# ZED-F9P_NEO-D9S_Combo.net
KiCad netlist of a schematic drawn in EAGLE
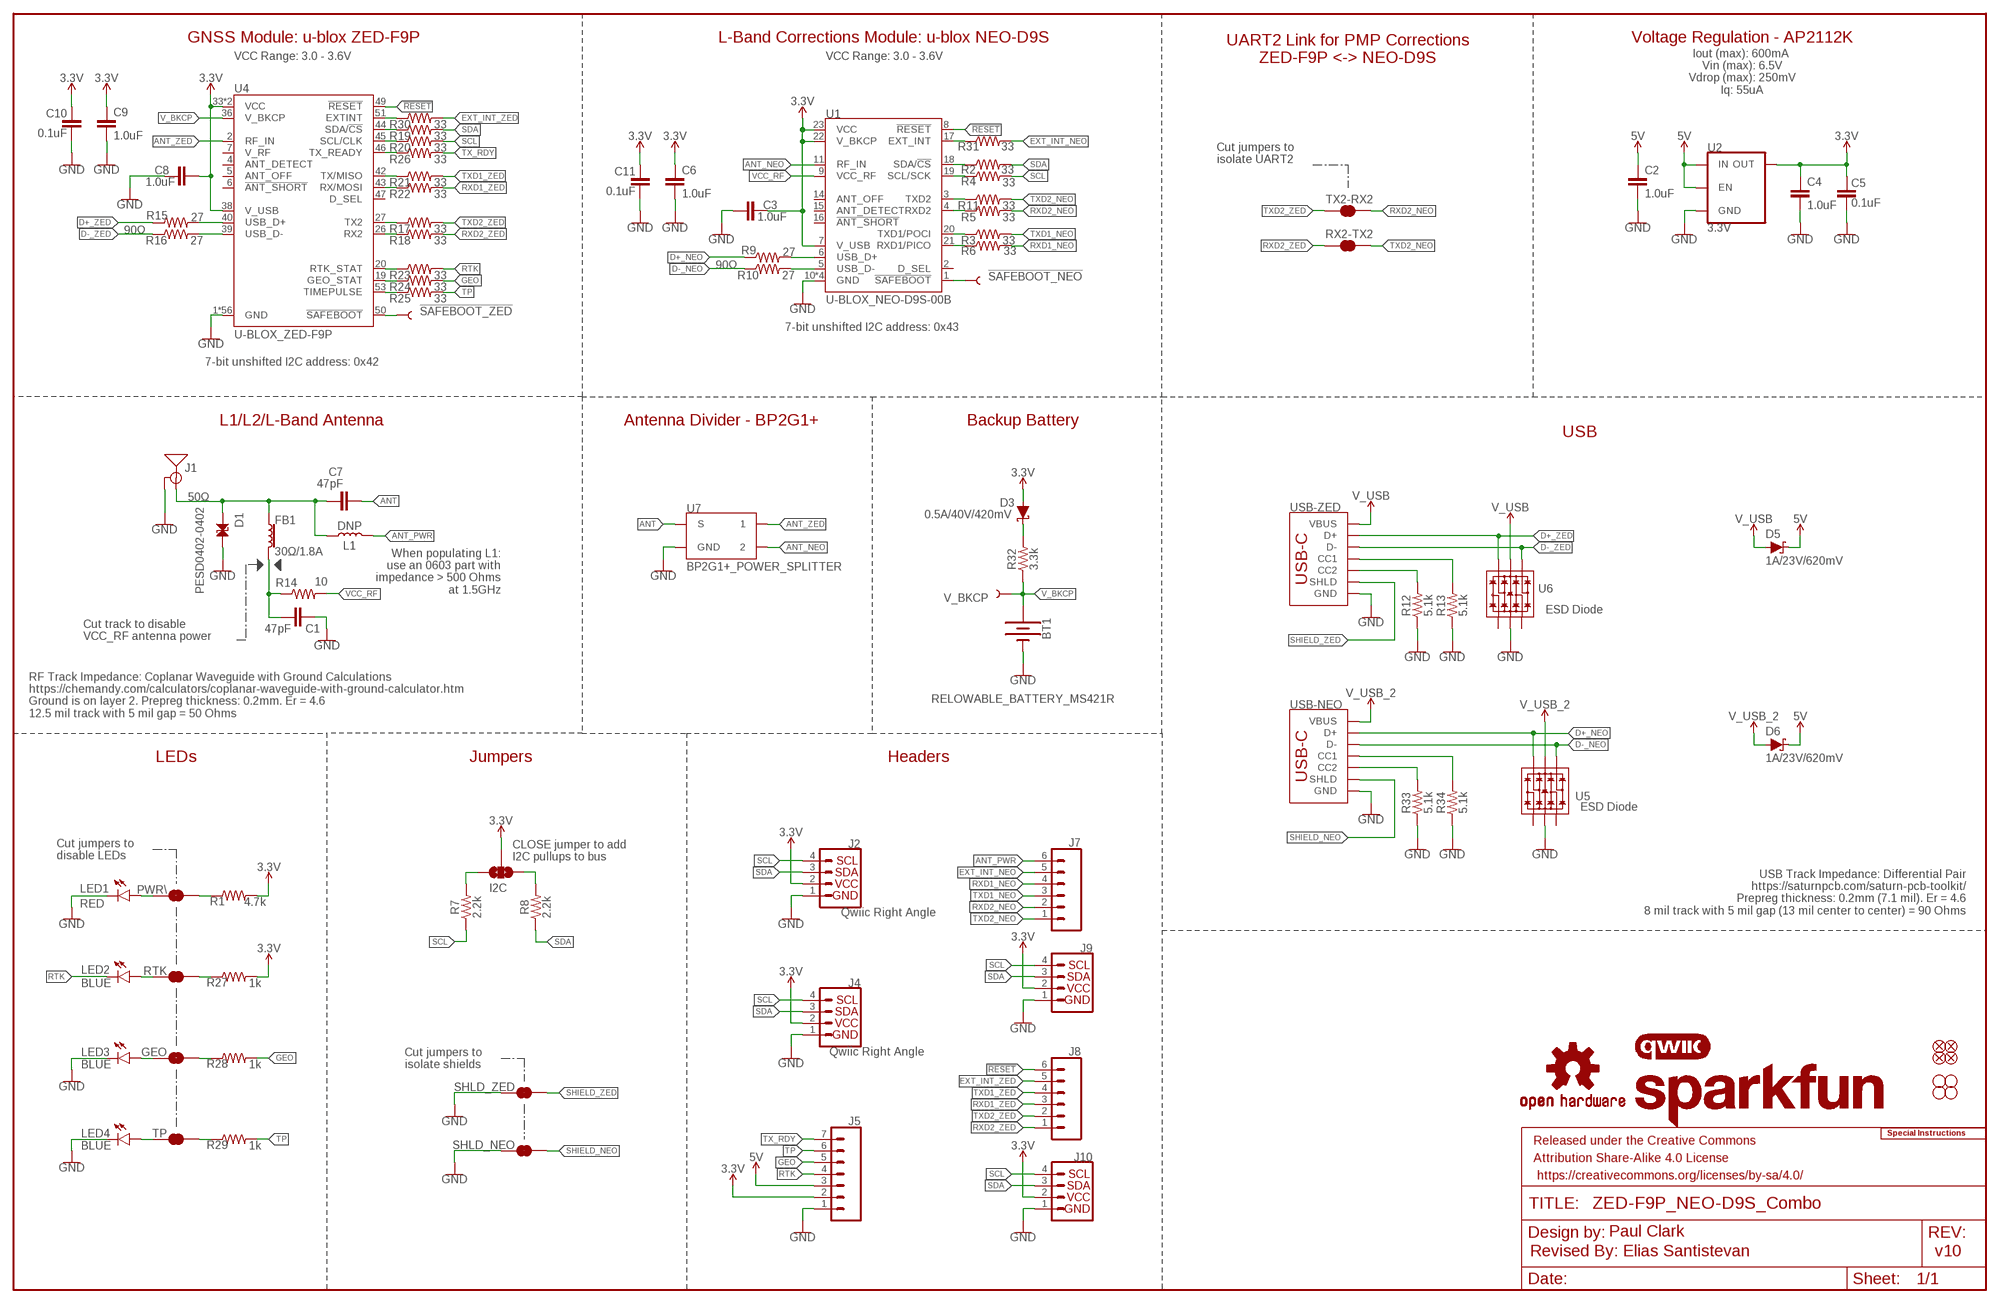
[diagram p0: schematic, sheet 1]

(export (version "E")
  (design (tool "Eeschema 10.0.6"))
  (components
    (comp (ref "!SAFEBOOT_NEO!")
      (value "TEST-POINTPOGO_PTH")
      (footprint "eagle-import:1X01_NO_SILK")
      (libsource (lib "eagle-import") (part "TEST-POINTPOGO_PTH"))
    )
    (comp (ref "!SAFEBOOT_ZED!")
      (value "TEST-POINTPOGO_PTH")
      (footprint "eagle-import:1X01_NO_SILK")
      (libsource (lib "eagle-import") (part "TEST-POINTPOGO_PTH"))
    )
    (comp (ref "BT1")
      (value "RELOWABLE_BATTERY_MS421R")
      (footprint "eagle-import:MS421R_IV03E")
      (libsource (lib "eagle-import") (part "RELOWABLE_BATTERY_MS421R"))
    )
    (comp (ref "C1")
      (value "47pF")
      (footprint "eagle-import:0603")
      (libsource (lib "eagle-import") (part "47PF-0603-50V-5%"))
    )
    (comp (ref "C2")
      (value "1.0uF")
      (footprint "eagle-import:0603")
      (libsource (lib "eagle-import") (part "1.0UF-0603-16V-10%"))
    )
    (comp (ref "C3")
      (value "1.0uF")
      (footprint "eagle-import:0603")
      (libsource (lib "eagle-import") (part "1.0UF-0603-16V-10%"))
    )
    (comp (ref "C4")
      (value "1.0uF")
      (footprint "eagle-import:0603")
      (libsource (lib "eagle-import") (part "1.0UF-0603-16V-10%"))
    )
    (comp (ref "C5")
      (value "0.1uF")
      (footprint "eagle-import:0603")
      (libsource (lib "eagle-import") (part "0.1UF-0603-25V-(+80/-20%)"))
    )
    (comp (ref "C6")
      (value "1.0uF")
      (footprint "eagle-import:0603")
      (libsource (lib "eagle-import") (part "1.0UF-0603-16V-10%"))
    )
    (comp (ref "C7")
      (value "47pF")
      (footprint "eagle-import:0603")
      (libsource (lib "eagle-import") (part "47PF-0603-50V-5%"))
    )
    (comp (ref "C8")
      (value "1.0uF")
      (footprint "eagle-import:0603")
      (libsource (lib "eagle-import") (part "1.0UF-0603-16V-10%"))
    )
    (comp (ref "C9")
      (value "1.0uF")
      (footprint "eagle-import:0603")
      (libsource (lib "eagle-import") (part "1.0UF-0603-16V-10%"))
    )
    (comp (ref "C10")
      (value "0.1uF")
      (footprint "eagle-import:0603")
      (libsource (lib "eagle-import") (part "0.1UF-0603-25V-(+80/-20%)"))
    )
    (comp (ref "C11")
      (value "0.1uF")
      (footprint "eagle-import:0603")
      (libsource (lib "eagle-import") (part "0.1UF-0603-25V-(+80/-20%)"))
    )
    (comp (ref "D1")
      (value "PESD0402-0402")
      (footprint "eagle-import:0402")
      (fields
        (field (name "DIGIKEY_PART") "PESD0402-140CT-ND")
        (field (name "MOUSE_PART") "650-PESD0402-140")
      )
      (libsource (lib "eagle-import") (part "PESD0402-0402"))
    )
    (comp (ref "D3")
      (value "0.5A/40V/420mV")
      (footprint "eagle-import:SOD-323")
      (libsource (lib "eagle-import") (part "DIODE-SCHOTTKY-PMEG4005EJ"))
    )
    (comp (ref "D5")
      (value "1A/23V/620mV")
      (footprint "eagle-import:SOD-323")
      (libsource (lib "eagle-import") (part "DIODE-SCHOTTKY-BAT20J"))
    )
    (comp (ref "D6")
      (value "1A/23V/620mV")
      (footprint "eagle-import:SOD-323")
      (libsource (lib "eagle-import") (part "DIODE-SCHOTTKY-BAT20J"))
    )
    (comp (ref "FB1")
      (value "30Ω/1.8A")
      (footprint "eagle-import:0603")
      (libsource (lib "eagle-import") (part "FERRITE_BEAD-0603"))
    )
    (comp (ref "FRAME2")
      (value "FRAME-LEDGER")
      (footprint "eagle-import:CREATIVE_COMMONS")
      (libsource (lib "eagle-import") (part "FRAME-LEDGER"))
    )
    (comp (ref "GEO")
      (value "JUMPER-SMT_2_NC_TRACE_SILK")
      (footprint "eagle-import:SMT-JUMPER_2_NC_TRACE_SILK")
      (libsource (lib "eagle-import") (part "JUMPER-SMT_2_NC_TRACE_SILK"))
    )
    (comp (ref "I2C")
      (value "JUMPER-SMT_3_NO_SILK")
      (footprint "eagle-import:SMT-JUMPER_3_NO_SILK")
      (libsource (lib "eagle-import") (part "JUMPER-SMT_3_NO_SILK"))
    )
    (comp (ref "J1")
      (value "ANTENNA-SMA-GROUNDEDEDGE_SMA")
      (footprint "eagle-import:SMA-EDGE")
      (libsource (lib "eagle-import") (part "ANTENNA-SMA-GROUNDEDEDGE_SMA"))
    )
    (comp (ref "J2")
      (value "Qwiic Right Angle")
      (footprint "eagle-import:JST04_1MM_RA")
      (libsource (lib "eagle-import") (part "I2C_STANDARDQWIIC"))
    )
    (comp (ref "J4")
      (value "Qwiic Right Angle")
      (footprint "eagle-import:JST04_1MM_RA")
      (libsource (lib "eagle-import") (part "I2C_STANDARDQWIIC"))
    )
    (comp (ref "J5")
      (value "CONN_07NO_SILK")
      (footprint "eagle-import:1X07_NO_SILK")
      (libsource (lib "eagle-import") (part "CONN_07NO_SILK"))
    )
    (comp (ref "J7")
      (value "CONN_06NO_SILK_NO_POP")
      (footprint "eagle-import:1X06_NO_SILK")
      (libsource (lib "eagle-import") (part "CONN_06NO_SILK_NO_POP"))
    )
    (comp (ref "J8")
      (value "CONN_06NO_SILK_NO_POP")
      (footprint "eagle-import:1X06_NO_SILK")
      (libsource (lib "eagle-import") (part "CONN_06NO_SILK_NO_POP"))
    )
    (comp (ref "J9")
      (value "I2C_STANDARD_NO_SILK")
      (footprint "eagle-import:1X04_NO_SILK")
      (libsource (lib "eagle-import") (part "I2C_STANDARD_NO_SILK"))
    )
    (comp (ref "J10")
      (value "I2C_STANDARD_NO_SILK")
      (footprint "eagle-import:1X04_NO_SILK")
      (libsource (lib "eagle-import") (part "I2C_STANDARD_NO_SILK"))
    )
    (comp (ref "JP21")
      (value "FIDUCIALUFIDUCIAL")
      (footprint "eagle-import:MICRO-FIDUCIAL")
      (libsource (lib "eagle-import") (part "FIDUCIALUFIDUCIAL"))
    )
    (comp (ref "JP31")
      (value "STAND-OFF")
      (footprint "eagle-import:STAND-OFF")
      (libsource (lib "eagle-import") (part "STAND-OFF"))
    )
    (comp (ref "JP41")
      (value "STAND-OFF")
      (footprint "eagle-import:STAND-OFF")
      (libsource (lib "eagle-import") (part "STAND-OFF"))
    )
    (comp (ref "JP61")
      (value "FIDUCIALUFIDUCIAL")
      (footprint "eagle-import:MICRO-FIDUCIAL")
      (libsource (lib "eagle-import") (part "FIDUCIALUFIDUCIAL"))
    )
    (comp (ref "JP71")
      (value "FIDUCIALUFIDUCIAL")
      (footprint "eagle-import:MICRO-FIDUCIAL")
      (libsource (lib "eagle-import") (part "FIDUCIALUFIDUCIAL"))
    )
    (comp (ref "JP81")
      (value "FIDUCIALUFIDUCIAL")
      (footprint "eagle-import:MICRO-FIDUCIAL")
      (libsource (lib "eagle-import") (part "FIDUCIALUFIDUCIAL"))
    )
    (comp (ref "JP91")
      (value "STAND-OFF")
      (footprint "eagle-import:STAND-OFF")
      (libsource (lib "eagle-import") (part "STAND-OFF"))
    )
    (comp (ref "JP101")
      (value "STAND-OFF")
      (footprint "eagle-import:STAND-OFF")
      (libsource (lib "eagle-import") (part "STAND-OFF"))
    )
    (comp (ref "L1")
      (value "DNP")
      (footprint "eagle-import:0603_NO-CREAM")
      (libsource (lib "eagle-import") (part "DNP-0603_NO-CREAM"))
    )
    (comp (ref "LED1")
      (value "RED")
      (footprint "eagle-import:LED-0603")
      (libsource (lib "eagle-import") (part "LED-RED_0603-KB"))
    )
    (comp (ref "LED2")
      (value "BLUE")
      (footprint "eagle-import:LED-0603")
      (libsource (lib "eagle-import") (part "LED-BLUE0603"))
    )
    (comp (ref "LED3")
      (value "BLUE")
      (footprint "eagle-import:LED-0603")
      (libsource (lib "eagle-import") (part "LED-BLUE0603"))
    )
    (comp (ref "LED4")
      (value "BLUE")
      (footprint "eagle-import:LED-0603")
      (libsource (lib "eagle-import") (part "LED-BLUE0603"))
    )
    (comp (ref "LOGO2")
      (value "SFE_LOGO_NAME.1_INCH")
      (footprint "eagle-import:SFE_LOGO_NAME_.1")
      (libsource (lib "eagle-import") (part "SFE_LOGO_NAME.1_INCH"))
    )
    (comp (ref "LOGO3")
      (value "QWIIC_LOGO_5MM")
      (footprint "eagle-import:QWIIC_5MM")
      (libsource (lib "eagle-import") (part "QWIIC_LOGO_5MM"))
    )
    (comp (ref "LOGO4")
      (value "OSHW-LOGOS")
      (footprint "eagle-import:OSHW-LOGO-S")
      (libsource (lib "eagle-import") (part "OSHW-LOGOS"))
    )
    (comp (ref "LOGO5")
      (value "SPECIAL_INSTRUCTIONS-ORDERING")
      (footprint "eagle-import:ORDERING_INSTRUCTIONS")
      (libsource (lib "eagle-import") (part "SPECIAL_INSTRUCTIONS-ORDERING"))
    )
    (comp (ref "PWR\\")
      (value "JUMPER-SMT_2_NC_TRACE_SILK")
      (footprint "eagle-import:SMT-JUMPER_2_NC_TRACE_SILK")
      (libsource (lib "eagle-import") (part "JUMPER-SMT_2_NC_TRACE_SILK"))
    )
    (comp (ref "R1")
      (value "4.7k")
      (footprint "eagle-import:0603")
      (libsource (lib "eagle-import") (part "4.7KOHM-0603-1/10W-1%"))
    )
    (comp (ref "R2")
      (value "33")
      (footprint "eagle-import:0603")
      (libsource (lib "eagle-import") (part "33OHM-0603-1/10W-1%"))
    )
    (comp (ref "R3")
      (value "33")
      (footprint "eagle-import:0603")
      (libsource (lib "eagle-import") (part "33OHM-0603-1/10W-1%"))
    )
    (comp (ref "R4")
      (value "33")
      (footprint "eagle-import:0603")
      (libsource (lib "eagle-import") (part "33OHM-0603-1/10W-1%"))
    )
    (comp (ref "R5")
      (value "33")
      (footprint "eagle-import:0603")
      (libsource (lib "eagle-import") (part "33OHM-0603-1/10W-1%"))
    )
    (comp (ref "R6")
      (value "33")
      (footprint "eagle-import:0603")
      (libsource (lib "eagle-import") (part "33OHM-0603-1/10W-1%"))
    )
    (comp (ref "R7")
      (value "2.2k")
      (footprint "eagle-import:0603")
      (libsource (lib "eagle-import") (part "2.2KOHM-0603-1/10W-1%"))
    )
    (comp (ref "R8")
      (value "2.2k")
      (footprint "eagle-import:0603")
      (libsource (lib "eagle-import") (part "2.2KOHM-0603-1/10W-1%"))
    )
    (comp (ref "R9")
      (value "27")
      (footprint "eagle-import:0603")
      (libsource (lib "eagle-import") (part "27OHM-0603-1/10W-1%"))
    )
    (comp (ref "R10")
      (value "27")
      (footprint "eagle-import:0603")
      (libsource (lib "eagle-import") (part "27OHM-0603-1/10W-1%"))
    )
    (comp (ref "R11")
      (value "33")
      (footprint "eagle-import:0603")
      (libsource (lib "eagle-import") (part "33OHM-0603-1/10W-1%"))
    )
    (comp (ref "R12")
      (value "5.1k")
      (footprint "eagle-import:0603")
      (libsource (lib "eagle-import") (part "5.1KOHM5.1KOHM-0603-1/10W-1%"))
    )
    (comp (ref "R13")
      (value "5.1k")
      (footprint "eagle-import:0603")
      (libsource (lib "eagle-import") (part "5.1KOHM5.1KOHM-0603-1/10W-1%"))
    )
    (comp (ref "R14")
      (value "10")
      (footprint "eagle-import:0603")
      (libsource (lib "eagle-import") (part "10OHM-0603-1/10W-1%"))
    )
    (comp (ref "R15")
      (value "27")
      (footprint "eagle-import:0603")
      (libsource (lib "eagle-import") (part "27OHM-0603-1/10W-1%"))
    )
    (comp (ref "R16")
      (value "27")
      (footprint "eagle-import:0603")
      (libsource (lib "eagle-import") (part "27OHM-0603-1/10W-1%"))
    )
    (comp (ref "R17")
      (value "33")
      (footprint "eagle-import:0603")
      (libsource (lib "eagle-import") (part "33OHM-0603-1/10W-1%"))
    )
    (comp (ref "R18")
      (value "33")
      (footprint "eagle-import:0603")
      (libsource (lib "eagle-import") (part "33OHM-0603-1/10W-1%"))
    )
    (comp (ref "R19")
      (value "33")
      (footprint "eagle-import:0603")
      (libsource (lib "eagle-import") (part "33OHM-0603-1/10W-1%"))
    )
    (comp (ref "R20")
      (value "33")
      (footprint "eagle-import:0603")
      (libsource (lib "eagle-import") (part "33OHM-0603-1/10W-1%"))
    )
    (comp (ref "R21")
      (value "33")
      (footprint "eagle-import:0603")
      (libsource (lib "eagle-import") (part "33OHM-0603-1/10W-1%"))
    )
    (comp (ref "R22")
      (value "33")
      (footprint "eagle-import:0603")
      (libsource (lib "eagle-import") (part "33OHM-0603-1/10W-1%"))
    )
    (comp (ref "R23")
      (value "33")
      (footprint "eagle-import:0603")
      (libsource (lib "eagle-import") (part "33OHM-0603-1/10W-1%"))
    )
    (comp (ref "R24")
      (value "33")
      (footprint "eagle-import:0603")
      (libsource (lib "eagle-import") (part "33OHM-0603-1/10W-1%"))
    )
    (comp (ref "R25")
      (value "33")
      (footprint "eagle-import:0603")
      (libsource (lib "eagle-import") (part "33OHM-0603-1/10W-1%"))
    )
    (comp (ref "R26")
      (value "33")
      (footprint "eagle-import:0603")
      (libsource (lib "eagle-import") (part "33OHM-0603-1/10W-1%"))
    )
    (comp (ref "R27")
      (value "1k")
      (footprint "eagle-import:0603")
      (libsource (lib "eagle-import") (part "1KOHM-0603-1/10W-1%"))
    )
    (comp (ref "R28")
      (value "1k")
      (footprint "eagle-import:0603")
      (libsource (lib "eagle-import") (part "1KOHM-0603-1/10W-1%"))
    )
    (comp (ref "R29")
      (value "1k")
      (footprint "eagle-import:0603")
      (libsource (lib "eagle-import") (part "1KOHM-0603-1/10W-1%"))
    )
    (comp (ref "R30")
      (value "33")
      (footprint "eagle-import:0603")
      (libsource (lib "eagle-import") (part "33OHM-0603-1/10W-1%"))
    )
    (comp (ref "R31")
      (value "33")
      (footprint "eagle-import:0603")
      (libsource (lib "eagle-import") (part "33OHM-0603-1/10W-1%"))
    )
    (comp (ref "R32")
      (value "3.3k")
      (footprint "eagle-import:0603")
      (libsource (lib "eagle-import") (part "3.3KOHM-0603-1/10W-1%"))
    )
    (comp (ref "R33")
      (value "5.1k")
      (footprint "eagle-import:0603")
      (libsource (lib "eagle-import") (part "5.1KOHM5.1KOHM-0603-1/10W-1%"))
    )
    (comp (ref "R34")
      (value "5.1k")
      (footprint "eagle-import:0603")
      (libsource (lib "eagle-import") (part "5.1KOHM5.1KOHM-0603-1/10W-1%"))
    )
    (comp (ref "RTK")
      (value "JUMPER-SMT_2_NC_TRACE_SILK")
      (footprint "eagle-import:SMT-JUMPER_2_NC_TRACE_SILK")
      (libsource (lib "eagle-import") (part "JUMPER-SMT_2_NC_TRACE_SILK"))
    )
    (comp (ref "RX2-TX2")
      (value "JUMPER-SMT_2_NC_TRACE_SILK")
      (footprint "eagle-import:SMT-JUMPER_2_NC_TRACE_SILK")
      (libsource (lib "eagle-import") (part "JUMPER-SMT_2_NC_TRACE_SILK"))
    )
    (comp (ref "SHLD_NEO")
      (value "JUMPER-SMT_2_NC_TRACE_SILK")
      (footprint "eagle-import:SMT-JUMPER_2_NC_TRACE_SILK")
      (libsource (lib "eagle-import") (part "JUMPER-SMT_2_NC_TRACE_SILK"))
    )
    (comp (ref "SHLD_ZED")
      (value "JUMPER-SMT_2_NC_TRACE_SILK")
      (footprint "eagle-import:SMT-JUMPER_2_NC_TRACE_SILK")
      (libsource (lib "eagle-import") (part "JUMPER-SMT_2_NC_TRACE_SILK"))
    )
    (comp (ref "TP")
      (value "JUMPER-SMT_2_NC_TRACE_SILK")
      (footprint "eagle-import:SMT-JUMPER_2_NC_TRACE_SILK")
      (libsource (lib "eagle-import") (part "JUMPER-SMT_2_NC_TRACE_SILK"))
    )
    (comp (ref "TX2-RX2")
      (value "JUMPER-SMT_2_NC_TRACE_SILK")
      (footprint "eagle-import:SMT-JUMPER_2_NC_TRACE_SILK")
      (libsource (lib "eagle-import") (part "JUMPER-SMT_2_NC_TRACE_SILK"))
    )
    (comp (ref "U1")
      (value "U-BLOX_NEO-D9S-00B")
      (footprint "eagle-import:NEO-M9N_M8T_M8U_D9S")
      (libsource (lib "eagle-import") (part "U-BLOX_NEO-D9S-00B"))
    )
    (comp (ref "U2")
      (value "3.3V")
      (footprint "eagle-import:SOT23-5")
      (libsource (lib "eagle-import") (part "V_REG_AP2112K-3.3V"))
    )
    (comp (ref "U4")
      (value "U-BLOX_ZED-F9P")
      (footprint "eagle-import:ZED-F9P")
      (libsource (lib "eagle-import") (part "U-BLOX_ZED-F9P"))
    )
    (comp (ref "U5")
      (value "ESD Diode")
      (footprint "eagle-import:SOT-23-6")
      (libsource (lib "eagle-import") (part "TVS_DIODE_ARRAY_DT1042-04SO-7"))
    )
    (comp (ref "U6")
      (value "ESD Diode")
      (footprint "eagle-import:SOT-23-6")
      (libsource (lib "eagle-import") (part "TVS_DIODE_ARRAY_DT1042-04SO-7"))
    )
    (comp (ref "U7")
      (value "BP2G1+_POWER_SPLITTER")
      (footprint "eagle-import:XX21")
      (libsource (lib "eagle-import") (part "BP2G1+_POWER_SPLITTER"))
    )
    (comp (ref "USB-NEO")
      (value "USB Female Type C Connector")
      (footprint "eagle-import:USB-C-16P_4LAYER-PADS")
      (libsource (lib "eagle-import") (part "USB_C_4-LAYER_PADS"))
    )
    (comp (ref "USB-ZED")
      (value "USB Female Type C Connector")
      (footprint "eagle-import:USB-C-16P_4LAYER-PADS")
      (libsource (lib "eagle-import") (part "USB_C_4-LAYER_PADS"))
    )
    (comp (ref "V_BKCP")
      (value "TEST-POINT3X5")
      (footprint "eagle-import:PAD.03X.05")
      (libsource (lib "eagle-import") (part "TEST-POINT3X5"))
    )
  )
  (nets
    (net (code "1") (name "/~{RESET}") (class "Default")
      (node (ref "J8") (pin "6") (pinfunction "6_6") (pintype "passive"))
      (node (ref "U1") (pin "8") (pinfunction "~{RESET}_8") (pintype "input"))
      (node (ref "U4") (pin "49") (pinfunction "~{RESET}_49") (pintype "bidirectional"))
    )
    (net (code "2") (name "3.3V") (class "Default")
      (node (ref "C10") (pin "2") (pinfunction "2_2") (pintype "passive"))
      (node (ref "C11") (pin "2") (pinfunction "2_2") (pintype "passive"))
      (node (ref "C3") (pin "1") (pinfunction "1_1") (pintype "passive"))
      (node (ref "C4") (pin "1") (pinfunction "1_1") (pintype "passive"))
      (node (ref "C5") (pin "2") (pinfunction "2_2") (pintype "passive"))
      (node (ref "C6") (pin "1") (pinfunction "1_1") (pintype "passive"))
      (node (ref "C8") (pin "2") (pinfunction "2_2") (pintype "passive"))
      (node (ref "C9") (pin "1") (pinfunction "1_1") (pintype "passive"))
      (node (ref "D3") (pin "A") (pinfunction "A_A") (pintype "passive"))
      (node (ref "I2C") (pin "2") (pinfunction "2_2") (pintype "passive"))
      (node (ref "J10") (pin "2") (pinfunction "2_2") (pintype "power_in"))
      (node (ref "J2") (pin "2") (pinfunction "2_2") (pintype "power_in"))
      (node (ref "J4") (pin "2") (pinfunction "2_2") (pintype "power_in"))
      (node (ref "J5") (pin "2") (pinfunction "2_2") (pintype "passive"))
      (node (ref "J9") (pin "2") (pinfunction "2_2") (pintype "power_in"))
      (node (ref "R1") (pin "2") (pinfunction "2_2") (pintype "passive"))
      (node (ref "R27") (pin "2") (pinfunction "2_2") (pintype "passive"))
      (node (ref "U1") (pin "22") (pinfunction "V_BKCP_22") (pintype "power_in"))
      (node (ref "U1") (pin "23") (pinfunction "VCC_23") (pintype "power_in"))
      (node (ref "U1") (pin "7") (pinfunction "V_USB_7") (pintype "power_in"))
      (node (ref "U2") (pin "5") (pinfunction "OUT_5") (pintype "passive"))
      (node (ref "U4") (pin "33") (pinfunction "VCC_33") (pintype "bidirectional"))
      (node (ref "U4") (pin "34") (pinfunction "VCC_34") (pintype "bidirectional"))
      (node (ref "U4") (pin "38") (pinfunction "V_USB_38") (pintype "bidirectional"))
    )
    (net (code "3") (name "5V") (class "Default")
      (node (ref "C2") (pin "1") (pinfunction "1_1") (pintype "passive"))
      (node (ref "D5") (pin "C") (pinfunction "C_C") (pintype "passive"))
      (node (ref "D6") (pin "C") (pinfunction "C_C") (pintype "passive"))
      (node (ref "J5") (pin "3") (pinfunction "3_3") (pintype "passive"))
      (node (ref "U2") (pin "1") (pinfunction "IN_1") (pintype "input"))
      (node (ref "U2") (pin "3") (pinfunction "EN_3") (pintype "input"))
    )
    (net (code "4") (name "ANT") (class "Default")
      (node (ref "C7") (pin "2") (pinfunction "2_2") (pintype "passive"))
      (node (ref "U7") (pin "2") (pinfunction "S_2") (pintype "bidirectional"))
    )
    (net (code "5") (name "ANT_NEO") (class "Default")
      (node (ref "U1") (pin "11") (pinfunction "RF_IN_11") (pintype "input"))
      (node (ref "U7") (pin "5") (pinfunction "2_5") (pintype "bidirectional"))
    )
    (net (code "6") (name "ANT_PWR") (class "Default")
      (node (ref "J7") (pin "6") (pinfunction "6_6") (pintype "passive"))
      (node (ref "L1") (pin "2") (pinfunction "2_2") (pintype "passive"))
    )
    (net (code "7") (name "ANT_ZED") (class "Default")
      (node (ref "U4") (pin "2") (pinfunction "RF_IN_2") (pintype "bidirectional"))
      (node (ref "U7") (pin "8") (pinfunction "1_8") (pintype "bidirectional"))
    )
    (net (code "8") (name "D+_NEO") (class "Default")
      (node (ref "R9") (pin "1") (pinfunction "1_1") (pintype "passive"))
      (node (ref "U5") (pin "6") (pinfunction "IO4_6") (pintype "bidirectional"))
      (node (ref "USB-NEO") (pin "A6") (pinfunction "D+_A6") (pintype "bidirectional"))
      (node (ref "USB-NEO") (pin "B6") (pinfunction "D+_B6") (pintype "bidirectional"))
    )
    (net (code "9") (name "D+_ZED") (class "Default")
      (node (ref "R15") (pin "1") (pinfunction "1_1") (pintype "passive"))
      (node (ref "U6") (pin "6") (pinfunction "IO4_6") (pintype "bidirectional"))
      (node (ref "USB-ZED") (pin "A6") (pinfunction "D+_A6") (pintype "bidirectional"))
      (node (ref "USB-ZED") (pin "B6") (pinfunction "D+_B6") (pintype "bidirectional"))
    )
    (net (code "10") (name "D-_NEO") (class "Default")
      (node (ref "R10") (pin "1") (pinfunction "1_1") (pintype "passive"))
      (node (ref "U5") (pin "4") (pinfunction "IO3_4") (pintype "bidirectional"))
      (node (ref "USB-NEO") (pin "A7") (pinfunction "D-_A7") (pintype "bidirectional"))
      (node (ref "USB-NEO") (pin "B7") (pinfunction "D-_B7") (pintype "bidirectional"))
    )
    (net (code "11") (name "D-_ZED") (class "Default")
      (node (ref "R16") (pin "1") (pinfunction "1_1") (pintype "passive"))
      (node (ref "U6") (pin "4") (pinfunction "IO3_4") (pintype "bidirectional"))
      (node (ref "USB-ZED") (pin "A7") (pinfunction "D-_A7") (pintype "bidirectional"))
      (node (ref "USB-ZED") (pin "B7") (pinfunction "D-_B7") (pintype "bidirectional"))
    )
    (net (code "12") (name "EXT_INT_NEO") (class "Default")
      (node (ref "J7") (pin "5") (pinfunction "5_5") (pintype "passive"))
      (node (ref "R31") (pin "2") (pinfunction "2_2") (pintype "passive"))
    )
    (net (code "13") (name "EXT_INT_ZED") (class "Default")
      (node (ref "J8") (pin "5") (pinfunction "5_5") (pintype "passive"))
      (node (ref "R30") (pin "2") (pinfunction "2_2") (pintype "passive"))
    )
    (net (code "14") (name "GEO") (class "Default")
      (node (ref "J5") (pin "5") (pinfunction "5_5") (pintype "passive"))
      (node (ref "R24") (pin "2") (pinfunction "2_2") (pintype "passive"))
      (node (ref "R28") (pin "2") (pinfunction "2_2") (pintype "passive"))
    )
    (net (code "15") (name "GND") (class "Default")
      (node (ref "BT1") (pin "-") (pinfunction "-_-") (pintype "power_in"))
      (node (ref "C1") (pin "2") (pinfunction "2_2") (pintype "passive"))
      (node (ref "C10") (pin "1") (pinfunction "1_1") (pintype "passive"))
      (node (ref "C11") (pin "1") (pinfunction "1_1") (pintype "passive"))
      (node (ref "C2") (pin "2") (pinfunction "2_2") (pintype "passive"))
      (node (ref "C3") (pin "2") (pinfunction "2_2") (pintype "passive"))
      (node (ref "C4") (pin "2") (pinfunction "2_2") (pintype "passive"))
      (node (ref "C5") (pin "1") (pinfunction "1_1") (pintype "passive"))
      (node (ref "C6") (pin "2") (pinfunction "2_2") (pintype "passive"))
      (node (ref "C8") (pin "1") (pinfunction "1_1") (pintype "passive"))
      (node (ref "C9") (pin "2") (pinfunction "2_2") (pintype "passive"))
      (node (ref "D1") (pin "2") (pinfunction "2_2") (pintype "bidirectional"))
      (node (ref "J1") (pin "GND@0") (pinfunction "GND_GND@0") (pintype "bidirectional"))
      (node (ref "J1") (pin "GND@1") (pinfunction "GND_GND@1") (pintype "bidirectional"))
      (node (ref "J1") (pin "GND@2") (pinfunction "GND_GND@2") (pintype "bidirectional"))
      (node (ref "J1") (pin "GND@3") (pinfunction "GND_GND@3") (pintype "bidirectional"))
      (node (ref "J10") (pin "1") (pinfunction "1_1") (pintype "power_in"))
      (node (ref "J2") (pin "1") (pinfunction "1_1") (pintype "power_in"))
      (node (ref "J4") (pin "1") (pinfunction "1_1") (pintype "power_in"))
      (node (ref "J5") (pin "1") (pinfunction "1_1") (pintype "passive"))
      (node (ref "J9") (pin "1") (pinfunction "1_1") (pintype "power_in"))
      (node (ref "LED1") (pin "C") (pinfunction "C_C") (pintype "passive"))
      (node (ref "LED3") (pin "C") (pinfunction "C_C") (pintype "passive"))
      (node (ref "LED4") (pin "C") (pinfunction "C_C") (pintype "passive"))
      (node (ref "R12") (pin "1") (pinfunction "1_1") (pintype "passive"))
      (node (ref "R13") (pin "1") (pinfunction "1_1") (pintype "passive"))
      (node (ref "R33") (pin "1") (pinfunction "1_1") (pintype "passive"))
      (node (ref "R34") (pin "1") (pinfunction "1_1") (pintype "passive"))
      (node (ref "SHLD_NEO") (pin "1") (pinfunction "1_1") (pintype "passive"))
      (node (ref "SHLD_ZED") (pin "1") (pinfunction "1_1") (pintype "passive"))
      (node (ref "U1") (pin "10") (pinfunction "GND_10") (pintype "power_in"))
      (node (ref "U1") (pin "12") (pinfunction "GND_12") (pintype "power_in"))
      (node (ref "U1") (pin "13") (pinfunction "GND_13") (pintype "power_in"))
      (node (ref "U1") (pin "24") (pinfunction "GND_24") (pintype "power_in"))
      (node (ref "U2") (pin "2") (pinfunction "GND_2") (pintype "input"))
      (node (ref "U4") (pin "1") (pinfunction "GND_1") (pintype "bidirectional"))
      (node (ref "U4") (pin "100") (pinfunction "GND_100") (pintype "bidirectional"))
      (node (ref "U4") (pin "101") (pinfunction "GND_101") (pintype "bidirectional"))
      (node (ref "U4") (pin "102") (pinfunction "GND_102") (pintype "bidirectional"))
      (node (ref "U4") (pin "12") (pinfunction "GND_12") (pintype "bidirectional"))
      (node (ref "U4") (pin "14") (pinfunction "GND_14") (pintype "bidirectional"))
      (node (ref "U4") (pin "3") (pinfunction "GND_3") (pintype "bidirectional"))
      (node (ref "U4") (pin "32") (pinfunction "GND_32") (pintype "bidirectional"))
      (node (ref "U4") (pin "37") (pinfunction "GND_37") (pintype "bidirectional"))
      (node (ref "U4") (pin "41") (pinfunction "GND_41") (pintype "bidirectional"))
      (node (ref "U4") (pin "48") (pinfunction "GND_48") (pintype "bidirectional"))
      (node (ref "U4") (pin "55") (pinfunction "GND_55") (pintype "bidirectional"))
      (node (ref "U4") (pin "56") (pinfunction "GND_56") (pintype "bidirectional"))
      (node (ref "U4") (pin "57") (pinfunction "GND_57") (pintype "bidirectional"))
      (node (ref "U4") (pin "58") (pinfunction "GND_58") (pintype "bidirectional"))
      (node (ref "U4") (pin "59") (pinfunction "GND_59") (pintype "bidirectional"))
      (node (ref "U4") (pin "60") (pinfunction "GND_60") (pintype "bidirectional"))
      (node (ref "U4") (pin "61") (pinfunction "GND_61") (pintype "bidirectional"))
      (node (ref "U4") (pin "62") (pinfunction "GND_62") (pintype "bidirectional"))
      (node (ref "U4") (pin "63") (pinfunction "GND_63") (pintype "bidirectional"))
      (node (ref "U4") (pin "64") (pinfunction "GND_64") (pintype "bidirectional"))
      (node (ref "U4") (pin "65") (pinfunction "GND_65") (pintype "bidirectional"))
      (node (ref "U4") (pin "66") (pinfunction "GND_66") (pintype "bidirectional"))
      (node (ref "U4") (pin "67") (pinfunction "GND_67") (pintype "bidirectional"))
      (node (ref "U4") (pin "68") (pinfunction "GND_68") (pintype "bidirectional"))
      (node (ref "U4") (pin "69") (pinfunction "GND_69") (pintype "bidirectional"))
      (node (ref "U4") (pin "70") (pinfunction "GND_70") (pintype "bidirectional"))
      (node (ref "U4") (pin "71") (pinfunction "GND_71") (pintype "bidirectional"))
      (node (ref "U4") (pin "72") (pinfunction "GND_72") (pintype "bidirectional"))
      (node (ref "U4") (pin "73") (pinfunction "GND_73") (pintype "bidirectional"))
      (node (ref "U4") (pin "74") (pinfunction "GND_74") (pintype "bidirectional"))
      (node (ref "U4") (pin "75") (pinfunction "GND_75") (pintype "bidirectional"))
      (node (ref "U4") (pin "76") (pinfunction "GND_76") (pintype "bidirectional"))
      (node (ref "U4") (pin "77") (pinfunction "GND_77") (pintype "bidirectional"))
      (node (ref "U4") (pin "78") (pinfunction "GND_78") (pintype "bidirectional"))
      (node (ref "U4") (pin "79") (pinfunction "GND_79") (pintype "bidirectional"))
      (node (ref "U4") (pin "80") (pinfunction "GND_80") (pintype "bidirectional"))
      (node (ref "U4") (pin "81") (pinfunction "GND_81") (pintype "bidirectional"))
      (node (ref "U4") (pin "82") (pinfunction "GND_82") (pintype "bidirectional"))
      (node (ref "U4") (pin "83") (pinfunction "GND_83") (pintype "bidirectional"))
      (node (ref "U4") (pin "84") (pinfunction "GND_84") (pintype "bidirectional"))
      (node (ref "U4") (pin "85") (pinfunction "GND_85") (pintype "bidirectional"))
      (node (ref "U4") (pin "86") (pinfunction "GND_86") (pintype "bidirectional"))
      (node (ref "U4") (pin "87") (pinfunction "GND_87") (pintype "bidirectional"))
      (node (ref "U4") (pin "88") (pinfunction "GND_88") (pintype "bidirectional"))
      (node (ref "U4") (pin "89") (pinfunction "GND_89") (pintype "bidirectional"))
      (node (ref "U4") (pin "90") (pinfunction "GND_90") (pintype "bidirectional"))
      (node (ref "U4") (pin "91") (pinfunction "GND_91") (pintype "bidirectional"))
      (node (ref "U4") (pin "92") (pinfunction "GND_92") (pintype "bidirectional"))
      (node (ref "U4") (pin "93") (pinfunction "GND_93") (pintype "bidirectional"))
      (node (ref "U4") (pin "94") (pinfunction "GND_94") (pintype "bidirectional"))
      (node (ref "U4") (pin "95") (pinfunction "GND_95") (pintype "bidirectional"))
      (node (ref "U4") (pin "96") (pinfunction "GND_96") (pintype "bidirectional"))
      (node (ref "U4") (pin "97") (pinfunction "GND_97") (pintype "bidirectional"))
      (node (ref "U4") (pin "98") (pinfunction "GND_98") (pintype "bidirectional"))
      (node (ref "U4") (pin "99") (pinfunction "GND_99") (pintype "bidirectional"))
      (node (ref "U5") (pin "2") (pinfunction "VSS_2") (pintype "bidirectional"))
      (node (ref "U6") (pin "2") (pinfunction "VSS_2") (pintype "bidirectional"))
      (node (ref "U7") (pin "1") (pinfunction "GND_1") (pintype "bidirectional"))
      (node (ref "U7") (pin "3") (pinfunction "GND_3") (pintype "bidirectional"))
      (node (ref "U7") (pin "4") (pinfunction "GND_4") (pintype "bidirectional"))
      (node (ref "U7") (pin "6") (pinfunction "GND_6") (pintype "bidirectional"))
      (node (ref "U7") (pin "7") (pinfunction "GND_7") (pintype "bidirectional"))
      (node (ref "USB-NEO") (pin "GND") (pinfunction "GND_GND") (pintype "bidirectional"))
      (node (ref "USB-NEO") (pin "GND2") (pinfunction "GND_GND2") (pintype "bidirectional"))
      (node (ref "USB-ZED") (pin "GND") (pinfunction "GND_GND") (pintype "bidirectional"))
      (node (ref "USB-ZED") (pin "GND2") (pinfunction "GND_GND2") (pintype "bidirectional"))
    )
    (net (code "16") (name "Net-(C1-Pad1)") (class "Default")
      (node (ref "C1") (pin "1") (pinfunction "1_1") (pintype "passive"))
      (node (ref "FB1") (pin "2") (pinfunction "2_2") (pintype "passive"))
      (node (ref "R14") (pin "1") (pinfunction "1_1") (pintype "passive"))
    )
    (net (code "17") (name "Net-(D3-PadC)") (class "Default")
      (node (ref "D3") (pin "C") (pinfunction "C_C") (pintype "passive"))
      (node (ref "R32") (pin "2") (pinfunction "2_2") (pintype "passive"))
    )
    (net (code "18") (name "Net-(GEO-Pad1)") (class "Default")
      (node (ref "GEO") (pin "1") (pinfunction "1_1") (pintype "passive"))
      (node (ref "LED3") (pin "A") (pinfunction "A_A") (pintype "passive"))
    )
    (net (code "19") (name "Net-(GEO-Pad2)") (class "Default")
      (node (ref "GEO") (pin "2") (pinfunction "2_2") (pintype "passive"))
      (node (ref "R28") (pin "1") (pinfunction "1_1") (pintype "passive"))
    )
    (net (code "20") (name "Net-(I2C-Pad1)") (class "Default")
      (node (ref "I2C") (pin "1") (pinfunction "1_1") (pintype "passive"))
      (node (ref "R8") (pin "2") (pinfunction "2_2") (pintype "passive"))
    )
    (net (code "21") (name "Net-(I2C-Pad3)") (class "Default")
      (node (ref "I2C") (pin "3") (pinfunction "3_3") (pintype "passive"))
      (node (ref "R7") (pin "2") (pinfunction "2_2") (pintype "passive"))
    )
    (net (code "22") (name "Net-(J1-SIGNAL)") (class "Default")
      (node (ref "C7") (pin "1") (pinfunction "1_1") (pintype "passive"))
      (node (ref "D1") (pin "1") (pinfunction "1_1") (pintype "bidirectional"))
      (node (ref "FB1") (pin "1") (pinfunction "1_1") (pintype "passive"))
      (node (ref "J1") (pin "SIG") (pinfunction "SIGNAL_SIG") (pintype "bidirectional"))
      (node (ref "L1") (pin "1") (pinfunction "1_1") (pintype "passive"))
    )
    (net (code "23") (name "Net-(LED1-PadA)") (class "Default")
      (node (ref "LED1") (pin "A") (pinfunction "A_A") (pintype "passive"))
      (node (ref "PWR\\") (pin "1") (pinfunction "1_1") (pintype "passive"))
    )
    (net (code "24") (name "Net-(LED2-PadA)") (class "Default")
      (node (ref "LED2") (pin "A") (pinfunction "A_A") (pintype "passive"))
      (node (ref "RTK") (pin "1") (pinfunction "1_1") (pintype "passive"))
    )
    (net (code "25") (name "Net-(LED4-PadA)") (class "Default")
      (node (ref "LED4") (pin "A") (pinfunction "A_A") (pintype "passive"))
      (node (ref "TP") (pin "1") (pinfunction "1_1") (pintype "passive"))
    )
    (net (code "26") (name "Net-(PWR\\-Pad2)") (class "Default")
      (node (ref "PWR\\") (pin "2") (pinfunction "2_2") (pintype "passive"))
      (node (ref "R1") (pin "1") (pinfunction "1_1") (pintype "passive"))
    )
    (net (code "27") (name "Net-(R27-Pad1)") (class "Default")
      (node (ref "R27") (pin "1") (pinfunction "1_1") (pintype "passive"))
      (node (ref "RTK") (pin "2") (pinfunction "2_2") (pintype "passive"))
    )
    (net (code "28") (name "Net-(R29-Pad1)") (class "Default")
      (node (ref "R29") (pin "1") (pinfunction "1_1") (pintype "passive"))
      (node (ref "TP") (pin "2") (pinfunction "2_2") (pintype "passive"))
    )
    (net (code "29") (name "Net-(U1-EXT_INT)") (class "Default")
      (node (ref "R31") (pin "1") (pinfunction "1_1") (pintype "passive"))
      (node (ref "U1") (pin "17") (pinfunction "EXT_INT_17") (pintype "input"))
    )
    (net (code "30") (name "Net-(U1-RXD1{slash}PICO)") (class "Default")
      (node (ref "R6") (pin "1") (pinfunction "1_1") (pintype "passive"))
      (node (ref "U1") (pin "21") (pinfunction "RXD1/PICO_21") (pintype "input"))
    )
    (net (code "31") (name "Net-(U1-RXD2)") (class "Default")
      (node (ref "R5") (pin "1") (pinfunction "1_1") (pintype "passive"))
      (node (ref "U1") (pin "4") (pinfunction "RXD2_4") (pintype "input"))
    )
    (net (code "32") (name "Net-(U1-SCL{slash}SCK)") (class "Default")
      (node (ref "R4") (pin "1") (pinfunction "1_1") (pintype "passive"))
      (node (ref "U1") (pin "19") (pinfunction "SCL/SCK_19") (pintype "bidirectional"))
    )
    (net (code "33") (name "Net-(U1-SDA{slash}~{CS})") (class "Default")
      (node (ref "R2") (pin "1") (pinfunction "1_1") (pintype "passive"))
      (node (ref "U1") (pin "18") (pinfunction "SDA/~{CS}_18") (pintype "bidirectional"))
    )
    (net (code "34") (name "Net-(U1-TXD1{slash}POCI)") (class "Default")
      (node (ref "R3") (pin "1") (pinfunction "1_1") (pintype "passive"))
      (node (ref "U1") (pin "20") (pinfunction "TXD1/POCI_20") (pintype "output"))
    )
    (net (code "35") (name "Net-(U1-TXD2)") (class "Default")
      (node (ref "R11") (pin "1") (pinfunction "1_1") (pintype "passive"))
      (node (ref "U1") (pin "3") (pinfunction "TXD2_3") (pintype "output"))
    )
    (net (code "36") (name "Net-(U1-USB_D+)") (class "Default")
      (node (ref "R9") (pin "2") (pinfunction "2_2") (pintype "passive"))
      (node (ref "U1") (pin "6") (pinfunction "USB_D+_6") (pintype "bidirectional"))
    )
    (net (code "37") (name "Net-(U1-USB_D-)") (class "Default")
      (node (ref "R10") (pin "2") (pinfunction "2_2") (pintype "passive"))
      (node (ref "U1") (pin "5") (pinfunction "USB_D-_5") (pintype "bidirectional"))
    )
    (net (code "38") (name "Net-(U1-~{SAFEBOOT})") (class "Default")
      (node (ref "!SAFEBOOT_NEO!") (pin "1") (pinfunction "1_1") (pintype "bidirectional"))
      (node (ref "U1") (pin "1") (pinfunction "~{SAFEBOOT}_1") (pintype "input"))
    )
    (net (code "39") (name "Net-(U4-EXTINT)") (class "Default")
      (node (ref "R30") (pin "1") (pinfunction "1_1") (pintype "passive"))
      (node (ref "U4") (pin "51") (pinfunction "EXTINT_51") (pintype "bidirectional"))
    )
    (net (code "40") (name "Net-(U4-GEO_STAT)") (class "Default")
      (node (ref "R24") (pin "1") (pinfunction "1_1") (pintype "passive"))
      (node (ref "U4") (pin "19") (pinfunction "GEO_STAT_19") (pintype "bidirectional"))
    )
    (net (code "41") (name "Net-(U4-RTK_STAT)") (class "Default")
      (node (ref "R23") (pin "1") (pinfunction "1_1") (pintype "passive"))
      (node (ref "U4") (pin "20") (pinfunction "RTK_STAT_20") (pintype "bidirectional"))
    )
    (net (code "42") (name "Net-(U4-RX2)") (class "Default")
      (node (ref "R18") (pin "1") (pinfunction "1_1") (pintype "passive"))
      (node (ref "U4") (pin "26") (pinfunction "RX2_26") (pintype "bidirectional"))
    )
    (net (code "43") (name "Net-(U4-RX{slash}MOSI)") (class "Default")
      (node (ref "R22") (pin "1") (pinfunction "1_1") (pintype "passive"))
      (node (ref "U4") (pin "43") (pinfunction "RX/MOSI_43") (pintype "bidirectional"))
    )
    (net (code "44") (name "Net-(U4-SCL{slash}CLK)") (class "Default")
      (node (ref "R20") (pin "1") (pinfunction "1_1") (pintype "passive"))
      (node (ref "U4") (pin "45") (pinfunction "SCL/CLK_45") (pintype "bidirectional"))
    )
    (net (code "45") (name "Net-(U4-SDA{slash}~{CS})") (class "Default")
      (node (ref "R19") (pin "1") (pinfunction "1_1") (pintype "passive"))
      (node (ref "U4") (pin "44") (pinfunction "SDA/~{CS}_44") (pintype "bidirectional"))
    )
    (net (code "46") (name "Net-(U4-TIMEPULSE)") (class "Default")
      (node (ref "R25") (pin "1") (pinfunction "1_1") (pintype "passive"))
      (node (ref "U4") (pin "53") (pinfunction "TIMEPULSE_53") (pintype "bidirectional"))
    )
    (net (code "47") (name "Net-(U4-TX2)") (class "Default")
      (node (ref "R17") (pin "1") (pinfunction "1_1") (pintype "passive"))
      (node (ref "U4") (pin "27") (pinfunction "TX2_27") (pintype "bidirectional"))
    )
    (net (code "48") (name "Net-(U4-TX_READY)") (class "Default")
      (node (ref "R26") (pin "1") (pinfunction "1_1") (pintype "passive"))
      (node (ref "U4") (pin "46") (pinfunction "TX_READY_46") (pintype "bidirectional"))
    )
    (net (code "49") (name "Net-(U4-TX{slash}MISO)") (class "Default")
      (node (ref "R21") (pin "1") (pinfunction "1_1") (pintype "passive"))
      (node (ref "U4") (pin "42") (pinfunction "TX/MISO_42") (pintype "bidirectional"))
    )
    (net (code "50") (name "Net-(U4-USB_D+)") (class "Default")
      (node (ref "R15") (pin "2") (pinfunction "2_2") (pintype "passive"))
      (node (ref "U4") (pin "40") (pinfunction "USB_D+_40") (pintype "bidirectional"))
    )
    (net (code "51") (name "Net-(U4-USB_D-)") (class "Default")
      (node (ref "R16") (pin "2") (pinfunction "2_2") (pintype "passive"))
      (node (ref "U4") (pin "39") (pinfunction "USB_D-_39") (pintype "bidirectional"))
    )
    (net (code "52") (name "Net-(U4-~{SAFEBOOT})") (class "Default")
      (node (ref "!SAFEBOOT_ZED!") (pin "1") (pinfunction "1_1") (pintype "bidirectional"))
      (node (ref "U4") (pin "50") (pinfunction "~{SAFEBOOT}_50") (pintype "bidirectional"))
    )
    (net (code "53") (name "Net-(USB-NEO-CC1)") (class "Default")
      (node (ref "R34") (pin "2") (pinfunction "2_2") (pintype "passive"))
      (node (ref "USB-NEO") (pin "A5") (pinfunction "CC1_A5") (pintype "bidirectional"))
    )
    (net (code "54") (name "Net-(USB-NEO-CC2)") (class "Default")
      (node (ref "R33") (pin "2") (pinfunction "2_2") (pintype "passive"))
      (node (ref "USB-NEO") (pin "B5") (pinfunction "CC2_B5") (pintype "bidirectional"))
    )
    (net (code "55") (name "Net-(USB-ZED-CC1)") (class "Default")
      (node (ref "R13") (pin "2") (pinfunction "2_2") (pintype "passive"))
      (node (ref "USB-ZED") (pin "A5") (pinfunction "CC1_A5") (pintype "bidirectional"))
    )
    (net (code "56") (name "Net-(USB-ZED-CC2)") (class "Default")
      (node (ref "R12") (pin "2") (pinfunction "2_2") (pintype "passive"))
      (node (ref "USB-ZED") (pin "B5") (pinfunction "CC2_B5") (pintype "bidirectional"))
    )
    (net (code "57") (name "RTK") (class "Default")
      (node (ref "J5") (pin "4") (pinfunction "4_4") (pintype "passive"))
      (node (ref "LED2") (pin "C") (pinfunction "C_C") (pintype "passive"))
      (node (ref "R23") (pin "2") (pinfunction "2_2") (pintype "passive"))
    )
    (net (code "58") (name "RXD1_NEO") (class "Default")
      (node (ref "J7") (pin "4") (pinfunction "4_4") (pintype "passive"))
      (node (ref "R6") (pin "2") (pinfunction "2_2") (pintype "passive"))
    )
    (net (code "59") (name "RXD1_ZED") (class "Default")
      (node (ref "J8") (pin "3") (pinfunction "3_3") (pintype "passive"))
      (node (ref "R22") (pin "2") (pinfunction "2_2") (pintype "passive"))
    )
    (net (code "60") (name "RXD2_NEO") (class "Default")
      (node (ref "J7") (pin "2") (pinfunction "2_2") (pintype "passive"))
      (node (ref "R5") (pin "2") (pinfunction "2_2") (pintype "passive"))
      (node (ref "TX2-RX2") (pin "2") (pinfunction "2_2") (pintype "passive"))
    )
    (net (code "61") (name "RXD2_ZED") (class "Default")
      (node (ref "J8") (pin "1") (pinfunction "1_1") (pintype "passive"))
      (node (ref "R18") (pin "2") (pinfunction "2_2") (pintype "passive"))
      (node (ref "RX2-TX2") (pin "1") (pinfunction "1_1") (pintype "passive"))
    )
    (net (code "62") (name "SCL") (class "Default")
      (node (ref "J10") (pin "4") (pinfunction "4_4") (pintype "passive"))
      (node (ref "J2") (pin "4") (pinfunction "4_4") (pintype "passive"))
      (node (ref "J4") (pin "4") (pinfunction "4_4") (pintype "passive"))
      (node (ref "J9") (pin "4") (pinfunction "4_4") (pintype "passive"))
      (node (ref "R20") (pin "2") (pinfunction "2_2") (pintype "passive"))
      (node (ref "R4") (pin "2") (pinfunction "2_2") (pintype "passive"))
      (node (ref "R7") (pin "1") (pinfunction "1_1") (pintype "passive"))
    )
    (net (code "63") (name "SDA") (class "Default")
      (node (ref "J10") (pin "3") (pinfunction "3_3") (pintype "passive"))
      (node (ref "J2") (pin "3") (pinfunction "3_3") (pintype "passive"))
      (node (ref "J4") (pin "3") (pinfunction "3_3") (pintype "passive"))
      (node (ref "J9") (pin "3") (pinfunction "3_3") (pintype "passive"))
      (node (ref "R19") (pin "2") (pinfunction "2_2") (pintype "passive"))
      (node (ref "R2") (pin "2") (pinfunction "2_2") (pintype "passive"))
      (node (ref "R8") (pin "1") (pinfunction "1_1") (pintype "passive"))
    )
    (net (code "64") (name "SHIELD_NEO") (class "Default")
      (node (ref "SHLD_NEO") (pin "2") (pinfunction "2_2") (pintype "passive"))
      (node (ref "USB-NEO") (pin "SHLD1") (pinfunction "SHLD_SHLD1") (pintype "bidirectional"))
      (node (ref "USB-NEO") (pin "SHLD2") (pinfunction "SHLD_SHLD2") (pintype "bidirectional"))
      (node (ref "USB-NEO") (pin "SHLD3") (pinfunction "SHLD_SHLD3") (pintype "bidirectional"))
      (node (ref "USB-NEO") (pin "SHLD4") (pinfunction "SHLD_SHLD4") (pintype "bidirectional"))
    )
    (net (code "65") (name "SHIELD_ZED") (class "Default")
      (node (ref "SHLD_ZED") (pin "2") (pinfunction "2_2") (pintype "passive"))
      (node (ref "USB-ZED") (pin "SHLD1") (pinfunction "SHLD_SHLD1") (pintype "bidirectional"))
      (node (ref "USB-ZED") (pin "SHLD2") (pinfunction "SHLD_SHLD2") (pintype "bidirectional"))
      (node (ref "USB-ZED") (pin "SHLD3") (pinfunction "SHLD_SHLD3") (pintype "bidirectional"))
      (node (ref "USB-ZED") (pin "SHLD4") (pinfunction "SHLD_SHLD4") (pintype "bidirectional"))
    )
    (net (code "66") (name "TP") (class "Default")
      (node (ref "J5") (pin "6") (pinfunction "6_6") (pintype "passive"))
      (node (ref "R25") (pin "2") (pinfunction "2_2") (pintype "passive"))
      (node (ref "R29") (pin "2") (pinfunction "2_2") (pintype "passive"))
    )
    (net (code "67") (name "TXD1_NEO") (class "Default")
      (node (ref "J7") (pin "3") (pinfunction "3_3") (pintype "passive"))
      (node (ref "R3") (pin "2") (pinfunction "2_2") (pintype "passive"))
    )
    (net (code "68") (name "TXD1_ZED") (class "Default")
      (node (ref "J8") (pin "4") (pinfunction "4_4") (pintype "passive"))
      (node (ref "R21") (pin "2") (pinfunction "2_2") (pintype "passive"))
    )
    (net (code "69") (name "TXD2_NEO") (class "Default")
      (node (ref "J7") (pin "1") (pinfunction "1_1") (pintype "passive"))
      (node (ref "R11") (pin "2") (pinfunction "2_2") (pintype "passive"))
      (node (ref "RX2-TX2") (pin "2") (pinfunction "2_2") (pintype "passive"))
    )
    (net (code "70") (name "TXD2_ZED") (class "Default")
      (node (ref "J8") (pin "2") (pinfunction "2_2") (pintype "passive"))
      (node (ref "R17") (pin "2") (pinfunction "2_2") (pintype "passive"))
      (node (ref "TX2-RX2") (pin "1") (pinfunction "1_1") (pintype "passive"))
    )
    (net (code "71") (name "TX_RDY") (class "Default")
      (node (ref "J5") (pin "7") (pinfunction "7_7") (pintype "passive"))
      (node (ref "R26") (pin "2") (pinfunction "2_2") (pintype "passive"))
    )
    (net (code "72") (name "VCC_RF") (class "Default")
      (node (ref "R14") (pin "2") (pinfunction "2_2") (pintype "passive"))
      (node (ref "U1") (pin "9") (pinfunction "VCC_RF_9") (pintype "output"))
    )
    (net (code "73") (name "V_BKCP") (class "Default")
      (node (ref "BT1") (pin "+") (pinfunction "+_+") (pintype "power_in"))
      (node (ref "R32") (pin "1") (pinfunction "1_1") (pintype "passive"))
      (node (ref "U4") (pin "36") (pinfunction "V_BKCP_36") (pintype "bidirectional"))
      (node (ref "V_BKCP") (pin "1") (pinfunction "1_1") (pintype "bidirectional"))
    )
    (net (code "74") (name "V_USB") (class "Default")
      (node (ref "D5") (pin "A") (pinfunction "A_A") (pintype "passive"))
      (node (ref "U6") (pin "5") (pinfunction "VCC_5") (pintype "bidirectional"))
      (node (ref "USB-ZED") (pin "VBUS1") (pinfunction "VBUS_VBUS1") (pintype "bidirectional"))
      (node (ref "USB-ZED") (pin "VBUS2") (pinfunction "VBUS_VBUS2") (pintype "bidirectional"))
    )
    (net (code "75") (name "V_USB_2") (class "Default")
      (node (ref "D6") (pin "A") (pinfunction "A_A") (pintype "passive"))
      (node (ref "U5") (pin "5") (pinfunction "VCC_5") (pintype "bidirectional"))
      (node (ref "USB-NEO") (pin "VBUS1") (pinfunction "VBUS_VBUS1") (pintype "bidirectional"))
      (node (ref "USB-NEO") (pin "VBUS2") (pinfunction "VBUS_VBUS2") (pintype "bidirectional"))
    )
    (net (code "76") (name "unconnected-(U1-ANT_DETECT-Pad15)") (class "Default")
      (node (ref "U1") (pin "15") (pinfunction "ANT_DETECT_15") (pintype "input"))
    )
    (net (code "77") (name "unconnected-(U1-ANT_OFF-Pad14)") (class "Default")
      (node (ref "U1") (pin "14") (pinfunction "ANT_OFF_14") (pintype "output"))
    )
    (net (code "78") (name "unconnected-(U1-D_SEL-Pad2)") (class "Default")
      (node (ref "U1") (pin "2") (pinfunction "D_SEL_2") (pintype "input"))
    )
    (net (code "79") (name "unconnected-(U1-~{ANT_SHORT}-Pad16)") (class "Default")
      (node (ref "U1") (pin "16") (pinfunction "~{ANT_SHORT}_16") (pintype "output"))
    )
    (net (code "80") (name "unconnected-(U4-ANT_DETECT-Pad4)") (class "Default")
      (node (ref "U4") (pin "4") (pinfunction "ANT_DETECT_4") (pintype "bidirectional"))
    )
    (net (code "81") (name "unconnected-(U4-ANT_OFF-Pad5)") (class "Default")
      (node (ref "U4") (pin "5") (pinfunction "ANT_OFF_5") (pintype "bidirectional"))
    )
    (net (code "82") (name "unconnected-(U4-D_SEL-Pad47)") (class "Default")
      (node (ref "U4") (pin "47") (pinfunction "D_SEL_47") (pintype "bidirectional"))
    )
    (net (code "83") (name "unconnected-(U4-V_RF-Pad7)") (class "Default")
      (node (ref "U4") (pin "7") (pinfunction "V_RF_7") (pintype "bidirectional"))
    )
    (net (code "84") (name "unconnected-(U4-~{ANT_SHORT}-Pad6)") (class "Default")
      (node (ref "U4") (pin "6") (pinfunction "~{ANT_SHORT}_6") (pintype "bidirectional"))
    )
    (net (code "85") (name "unconnected-(U5-IO1-Pad1)") (class "Default")
      (node (ref "U5") (pin "1") (pinfunction "IO1_1") (pintype "bidirectional"))
    )
    (net (code "86") (name "unconnected-(U5-IO2-Pad3)") (class "Default")
      (node (ref "U5") (pin "3") (pinfunction "IO2_3") (pintype "bidirectional"))
    )
    (net (code "87") (name "unconnected-(U6-IO1-Pad1)") (class "Default")
      (node (ref "U6") (pin "1") (pinfunction "IO1_1") (pintype "bidirectional"))
    )
    (net (code "88") (name "unconnected-(U6-IO2-Pad3)") (class "Default")
      (node (ref "U6") (pin "3") (pinfunction "IO2_3") (pintype "bidirectional"))
    )
  )
)
